# nrfMysensor.net
KiCad netlist of a schematic drawn in EAGLE
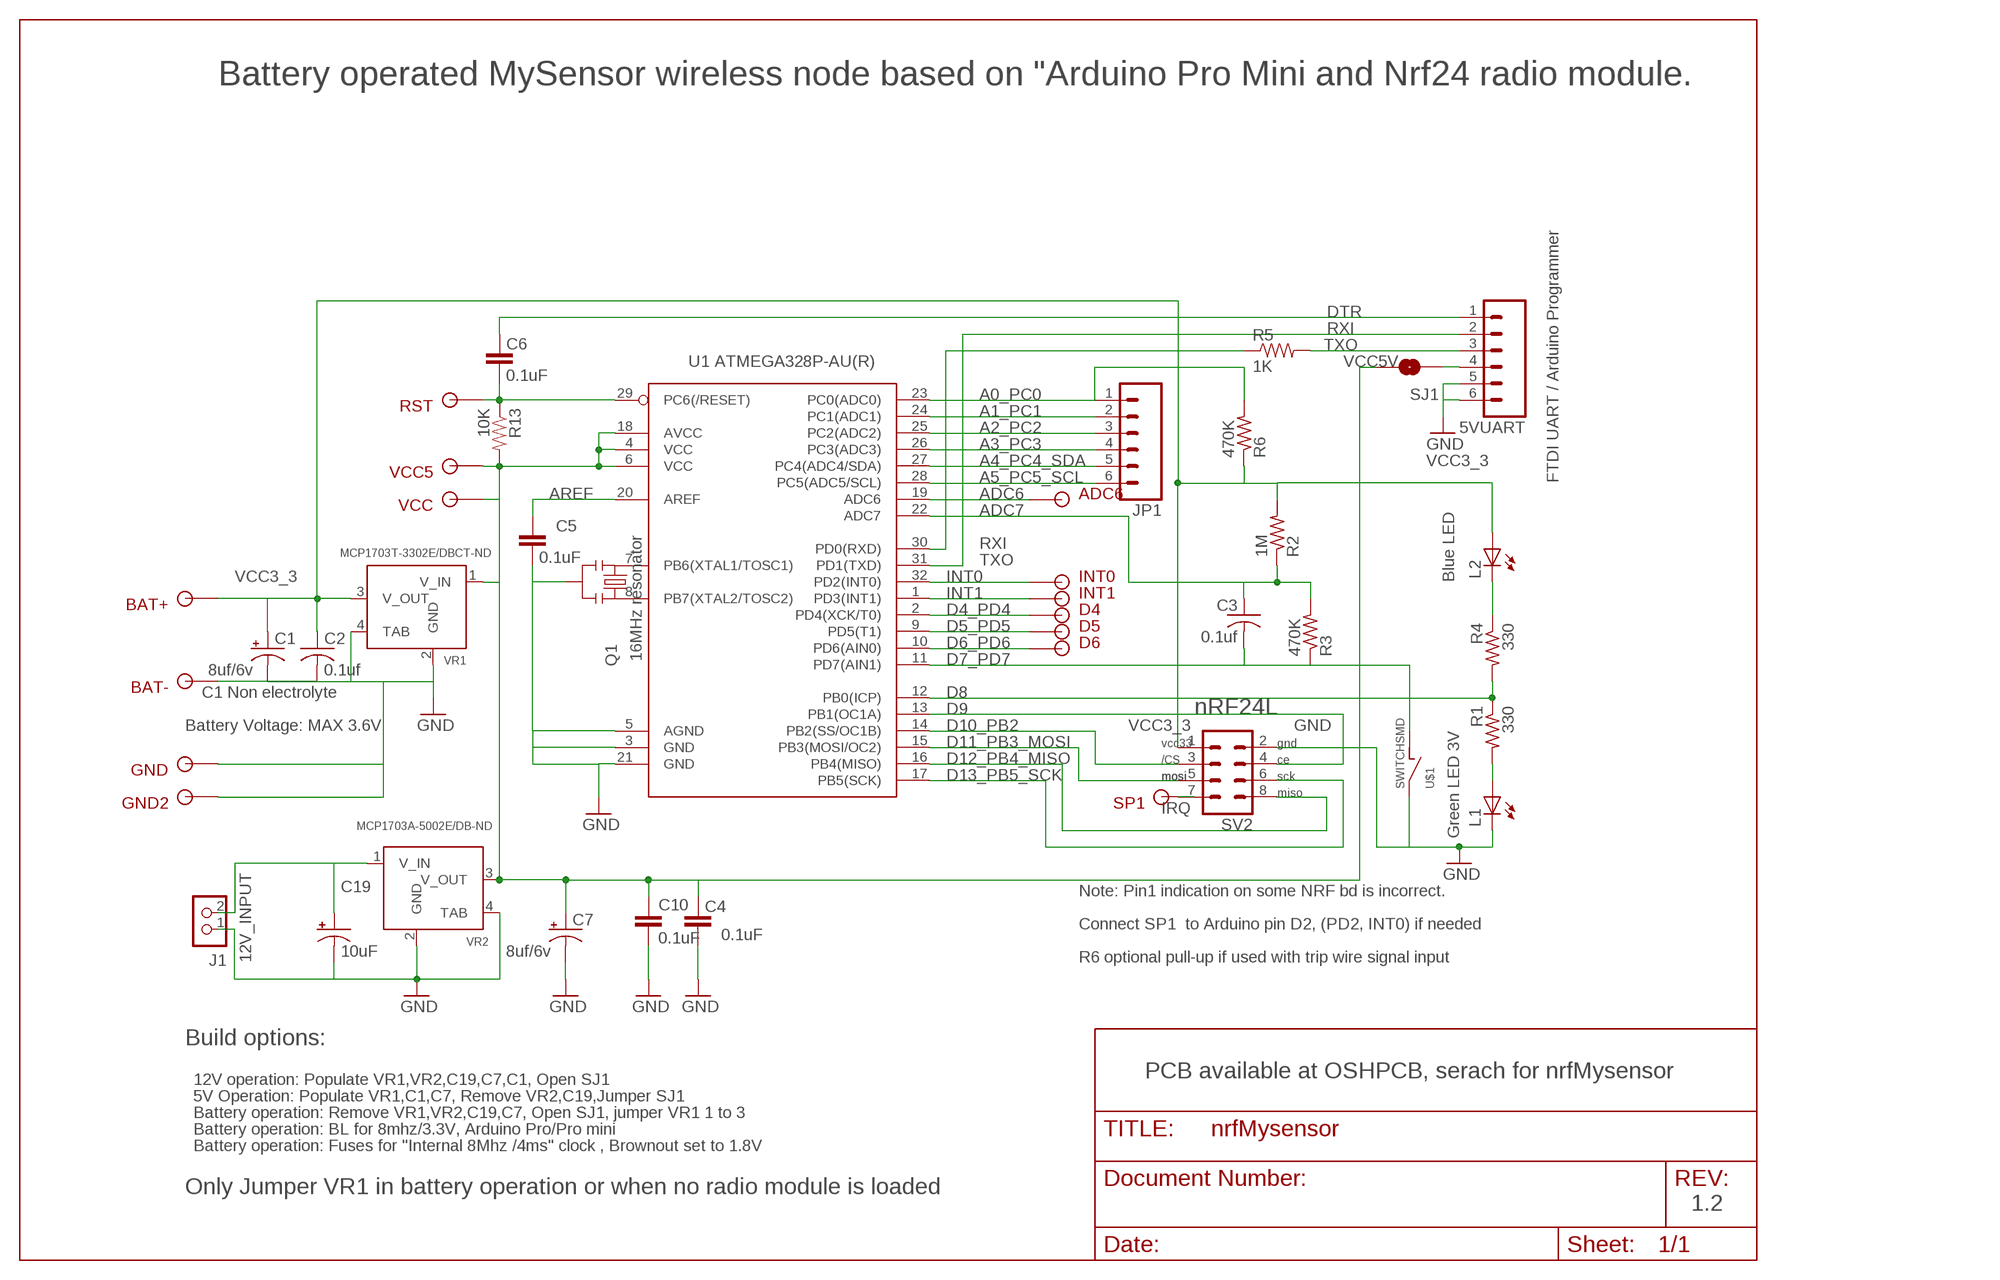
[diagram p0: schematic, sheet 1]

(export (version "E")
  (design (tool "Eeschema 10.0.6"))
  (components
    (comp (ref "5VUART")
      (value "M06SIP")
      (footprint "eagle-import:1X06")
      (libsource (lib "eagle-import") (part "M06SIP"))
    )
    (comp (ref "ADC6")
      (value "SOLDER_POINTA")
      (footprint "eagle-import:P1-13")
      (libsource (lib "eagle-import") (part "SOLDER_POINTA"))
    )
    (comp (ref "BAT+")
      (value "SOLDER_POINTA")
      (footprint "eagle-import:P1-13")
      (libsource (lib "eagle-import") (part "SOLDER_POINTA"))
    )
    (comp (ref "BAT-")
      (value "SOLDER_POINTA")
      (footprint "eagle-import:P1-13")
      (libsource (lib "eagle-import") (part "SOLDER_POINTA"))
    )
    (comp (ref "C1")
      (value "8uf/6v")
      (footprint "eagle-import:SMC_B")
      (libsource (lib "eagle-import") (part "CPOL-USSMCB"))
    )
    (comp (ref "C2")
      (value "0.1uf")
      (footprint "eagle-import:C0805")
      (libsource (lib "eagle-import") (part "C-USC0805"))
    )
    (comp (ref "C3")
      (value "0.1uf")
      (footprint "eagle-import:C0805")
      (libsource (lib "eagle-import") (part "C-USC0805"))
    )
    (comp (ref "C4")
      (value "0.1uF")
      (footprint "eagle-import:0805")
      (libsource (lib "eagle-import") (part "CAP0805"))
    )
    (comp (ref "C5")
      (value "0.1uF")
      (footprint "eagle-import:0805")
      (libsource (lib "eagle-import") (part "CAP0805"))
    )
    (comp (ref "C6")
      (value "0.1uF")
      (footprint "eagle-import:0805")
      (libsource (lib "eagle-import") (part "CAP0805"))
    )
    (comp (ref "C7")
      (value "8uf/6v")
      (footprint "eagle-import:SMC_B")
      (libsource (lib "eagle-import") (part "CPOL-USSMCB"))
    )
    (comp (ref "C10")
      (value "0.1uF")
      (footprint "eagle-import:0805")
      (libsource (lib "eagle-import") (part "CAP0805"))
    )
    (comp (ref "C19")
      (value "10uF")
      (footprint "eagle-import:EIA7343")
      (libsource (lib "eagle-import") (part "CAP_POL7343"))
    )
    (comp (ref "D4")
      (value "SOLDER_POINTA")
      (footprint "eagle-import:P1-13")
      (libsource (lib "eagle-import") (part "SOLDER_POINTA"))
    )
    (comp (ref "D5")
      (value "SOLDER_POINTA")
      (footprint "eagle-import:P1-13")
      (libsource (lib "eagle-import") (part "SOLDER_POINTA"))
    )
    (comp (ref "D6")
      (value "SOLDER_POINTA")
      (footprint "eagle-import:P1-13")
      (libsource (lib "eagle-import") (part "SOLDER_POINTA"))
    )
    (comp (ref "GND")
      (value "SOLDER_POINTA")
      (footprint "eagle-import:P1-13")
      (libsource (lib "eagle-import") (part "SOLDER_POINTA"))
    )
    (comp (ref "GND2")
      (value "SOLDER_POINTA")
      (footprint "eagle-import:P1-13")
      (libsource (lib "eagle-import") (part "SOLDER_POINTA"))
    )
    (comp (ref "INT0")
      (value "SOLDER_POINTA")
      (footprint "eagle-import:P1-13")
      (libsource (lib "eagle-import") (part "SOLDER_POINTA"))
    )
    (comp (ref "INT1")
      (value "SOLDER_POINTA")
      (footprint "eagle-import:P1-13")
      (libsource (lib "eagle-import") (part "SOLDER_POINTA"))
    )
    (comp (ref "J1")
      (value "12V input")
      (footprint "eagle-import:M1X2")
      (libsource (lib "eagle-import") (part "CON_HEADER_1X02-PTH"))
    )
    (comp (ref "JP1")
      (value "M06SIP")
      (footprint "eagle-import:1X06")
      (libsource (lib "eagle-import") (part "M06SIP"))
    )
    (comp (ref "L1")
      (value "LEDSML0603")
      (footprint "eagle-import:SML0603")
      (libsource (lib "eagle-import") (part "LEDSML0603"))
    )
    (comp (ref "L2")
      (value "LEDSML0603")
      (footprint "eagle-import:SML0603")
      (libsource (lib "eagle-import") (part "LEDSML0603"))
    )
    (comp (ref "Q1")
      (value "16MHz resonator")
      (footprint "eagle-import:RESONATOR-SMD")
      (libsource (lib "eagle-import") (part "RESONATORSMD"))
    )
    (comp (ref "R1")
      (value "330")
      (footprint "eagle-import:R0603")
      (libsource (lib "eagle-import") (part "R-US_R0603"))
    )
    (comp (ref "R2")
      (value "1M")
      (footprint "eagle-import:R0603")
      (libsource (lib "eagle-import") (part "R-US_R0603"))
    )
    (comp (ref "R3")
      (value "470K")
      (footprint "eagle-import:R0603")
      (libsource (lib "eagle-import") (part "R-US_R0603"))
    )
    (comp (ref "R4")
      (value "330")
      (footprint "eagle-import:R0603")
      (libsource (lib "eagle-import") (part "R-US_R0603"))
    )
    (comp (ref "R5")
      (value "1K")
      (footprint "eagle-import:0603")
      (libsource (lib "eagle-import") (part "RESISTOR0603"))
    )
    (comp (ref "R6")
      (value "470K")
      (footprint "eagle-import:R0603")
      (libsource (lib "eagle-import") (part "R-US_R0603"))
    )
    (comp (ref "R13")
      (value "10K")
      (footprint "eagle-import:0603")
      (libsource (lib "eagle-import") (part "RESISTOR0603"))
    )
    (comp (ref "RST")
      (value "SOLDER_POINTA")
      (footprint "eagle-import:P1-13")
      (libsource (lib "eagle-import") (part "SOLDER_POINTA"))
    )
    (comp (ref "SJ1")
      (value "SOLDERJUMPERNO")
      (footprint "eagle-import:SJ_2S-NO")
      (libsource (lib "eagle-import") (part "SOLDERJUMPERNO"))
    )
    (comp (ref "SP1")
      (value "SOLDER_POINTA")
      (footprint "eagle-import:P1-13")
      (libsource (lib "eagle-import") (part "SOLDER_POINTA"))
    )
    (comp (ref "SV2")
      (value "MA04-2")
      (footprint "eagle-import:MA04-2")
      (libsource (lib "eagle-import") (part "MA04-2"))
    )
    (comp (ref "U$1")
      (value "SWITCHSMD")
      (footprint "eagle-import:SMD_SWITCH")
      (libsource (lib "eagle-import") (part "SWITCHSMD"))
    )
    (comp (ref "U1")
      (value "ATMEGA328P-AU(R)")
      (footprint "eagle-import:TQFP32-08")
      (libsource (lib "eagle-import") (part "ATMEGA168"))
    )
    (comp (ref "VCC")
      (value "SOLDER_POINTA")
      (footprint "eagle-import:P1-13")
      (libsource (lib "eagle-import") (part "SOLDER_POINTA"))
    )
    (comp (ref "VCC5")
      (value "SOLDER_POINTA")
      (footprint "eagle-import:P1-13")
      (libsource (lib "eagle-import") (part "SOLDER_POINTA"))
    )
    (comp (ref "VR1")
      (value "MCP1703T-3302E/DBCT-ND")
      (footprint "eagle-import:SOT223")
      (libsource (lib "eagle-import") (part "MCP1703ASOT223"))
    )
    (comp (ref "VR2")
      (value "MCP1703A-5002E/DB-ND")
      (footprint "eagle-import:SOT223")
      (libsource (lib "eagle-import") (part "MCP1703ASOT223"))
    )
  )
  (nets
    (net (code "1") (name "/12V_INPUT") (class "Default")
      (node (ref "C19") (pin "A") (pinfunction "+_A") (pintype "passive"))
      (node (ref "J1") (pin "2") (pinfunction "2_2") (pintype "passive"))
      (node (ref "VR2") (pin "1") (pinfunction "V_IN_1") (pintype "bidirectional"))
    )
    (net (code "2") (name "/A0_PC0") (class "Default")
      (node (ref "JP1") (pin "1") (pinfunction "1_1") (pintype "passive"))
      (node (ref "R6") (pin "2") (pinfunction "2_2") (pintype "passive"))
      (node (ref "U1") (pin "23") (pinfunction "PC0(ADC0)_23") (pintype "bidirectional"))
    )
    (net (code "3") (name "/A1_PC1") (class "Default")
      (node (ref "JP1") (pin "2") (pinfunction "2_2") (pintype "passive"))
      (node (ref "U1") (pin "24") (pinfunction "PC1(ADC1)_24") (pintype "bidirectional"))
    )
    (net (code "4") (name "/A2_PC2") (class "Default")
      (node (ref "JP1") (pin "3") (pinfunction "3_3") (pintype "passive"))
      (node (ref "U1") (pin "25") (pinfunction "PC2(ADC2)_25") (pintype "bidirectional"))
    )
    (net (code "5") (name "/A3_PC3") (class "Default")
      (node (ref "JP1") (pin "4") (pinfunction "4_4") (pintype "passive"))
      (node (ref "U1") (pin "26") (pinfunction "PC3(ADC3)_26") (pintype "bidirectional"))
    )
    (net (code "6") (name "/A4_PC4_SDA") (class "Default")
      (node (ref "JP1") (pin "5") (pinfunction "5_5") (pintype "passive"))
      (node (ref "U1") (pin "27") (pinfunction "PC4(ADC4/SDA)_27") (pintype "bidirectional"))
    )
    (net (code "7") (name "/A5_PC5_SCL") (class "Default")
      (node (ref "JP1") (pin "6") (pinfunction "6_6") (pintype "passive"))
      (node (ref "U1") (pin "28") (pinfunction "PC5(ADC5/SCL)_28") (pintype "bidirectional"))
    )
    (net (code "8") (name "/ADC6") (class "Default")
      (node (ref "ADC6") (pin "1") (pinfunction "P$1_1") (pintype "bidirectional"))
      (node (ref "U1") (pin "19") (pinfunction "ADC6_19") (pintype "bidirectional"))
    )
    (net (code "9") (name "/ADC7") (class "Default")
      (node (ref "C3") (pin "1") (pinfunction "1_1") (pintype "passive"))
      (node (ref "R2") (pin "1") (pinfunction "1_1") (pintype "passive"))
      (node (ref "R3") (pin "2") (pinfunction "2_2") (pintype "passive"))
      (node (ref "U1") (pin "22") (pinfunction "ADC7_22") (pintype "bidirectional"))
    )
    (net (code "10") (name "/AREF") (class "Default")
      (node (ref "C5") (pin "2") (pinfunction "2_2") (pintype "passive"))
      (node (ref "U1") (pin "20") (pinfunction "AREF_20") (pintype "bidirectional"))
    )
    (net (code "11") (name "/D4_PD4") (class "Default")
      (node (ref "D4") (pin "1") (pinfunction "P$1_1") (pintype "bidirectional"))
      (node (ref "U1") (pin "2") (pinfunction "PD4(XCK/T0)_2") (pintype "bidirectional"))
    )
    (net (code "12") (name "/D5_PD5") (class "Default")
      (node (ref "D5") (pin "1") (pinfunction "P$1_1") (pintype "bidirectional"))
      (node (ref "U1") (pin "9") (pinfunction "PD5(T1)_9") (pintype "bidirectional"))
    )
    (net (code "13") (name "/D6_PD6") (class "Default")
      (node (ref "D6") (pin "1") (pinfunction "P$1_1") (pintype "bidirectional"))
      (node (ref "U1") (pin "10") (pinfunction "PD6(AIN0)_10") (pintype "bidirectional"))
    )
    (net (code "14") (name "/D7_PD7") (class "Default")
      (node (ref "C3") (pin "2") (pinfunction "2_2") (pintype "passive"))
      (node (ref "R3") (pin "1") (pinfunction "1_1") (pintype "passive"))
      (node (ref "U$1") (pin "P$1") (pinfunction "P$1_P$1") (pintype "passive"))
      (node (ref "U1") (pin "11") (pinfunction "PD7(AIN1)_11") (pintype "bidirectional"))
    )
    (net (code "15") (name "/D8") (class "Default")
      (node (ref "R1") (pin "1") (pinfunction "1_1") (pintype "passive"))
      (node (ref "R4") (pin "2") (pinfunction "2_2") (pintype "passive"))
      (node (ref "U1") (pin "12") (pinfunction "PB0(ICP)_12") (pintype "bidirectional"))
    )
    (net (code "16") (name "/D9") (class "Default")
      (node (ref "SV2") (pin "4") (pinfunction "4_4") (pintype "passive"))
      (node (ref "U1") (pin "13") (pinfunction "PB1(OC1A)_13") (pintype "bidirectional"))
    )
    (net (code "17") (name "/D10_PB2") (class "Default")
      (node (ref "SV2") (pin "3") (pinfunction "3_3") (pintype "passive"))
      (node (ref "U1") (pin "14") (pinfunction "PB2(SS/OC1B)_14") (pintype "bidirectional"))
    )
    (net (code "18") (name "/D11_PB3_MOSI") (class "Default")
      (node (ref "SV2") (pin "5") (pinfunction "5_5") (pintype "passive"))
      (node (ref "U1") (pin "15") (pinfunction "PB3(MOSI/OC2)_15") (pintype "bidirectional"))
    )
    (net (code "19") (name "/D12_PB4_MISO") (class "Default")
      (node (ref "SV2") (pin "8") (pinfunction "8_8") (pintype "passive"))
      (node (ref "U1") (pin "16") (pinfunction "PB4(MISO)_16") (pintype "bidirectional"))
    )
    (net (code "20") (name "/D13_PB5_SCK") (class "Default")
      (node (ref "SV2") (pin "6") (pinfunction "6_6") (pintype "passive"))
      (node (ref "U1") (pin "17") (pinfunction "PB5(SCK)_17") (pintype "bidirectional"))
    )
    (net (code "21") (name "/INT0") (class "Default")
      (node (ref "INT0") (pin "1") (pinfunction "P$1_1") (pintype "bidirectional"))
      (node (ref "U1") (pin "32") (pinfunction "PD2(INT0)_32") (pintype "bidirectional"))
    )
    (net (code "22") (name "/INT1") (class "Default")
      (node (ref "INT1") (pin "1") (pinfunction "P$1_1") (pintype "bidirectional"))
      (node (ref "U1") (pin "1") (pinfunction "PD3(INT1)_1") (pintype "bidirectional"))
    )
    (net (code "23") (name "/IRQ") (class "Default")
      (node (ref "SP1") (pin "1") (pinfunction "P$1_1") (pintype "bidirectional"))
      (node (ref "SV2") (pin "7") (pinfunction "7_7") (pintype "passive"))
    )
    (net (code "24") (name "/RXI") (class "Default")
      (node (ref "R5") (pin "1") (pinfunction "1_1") (pintype "passive"))
      (node (ref "U1") (pin "30") (pinfunction "PD0(RXD)_30") (pintype "bidirectional"))
    )
    (net (code "25") (name "/TXO") (class "Default")
      (node (ref "5VUART") (pin "2") (pinfunction "2_2") (pintype "passive"))
      (node (ref "U1") (pin "31") (pinfunction "PD1(TXD)_31") (pintype "bidirectional"))
    )
    (net (code "26") (name "/VCC3_3") (class "Default")
      (node (ref "BAT+") (pin "1") (pinfunction "P$1_1") (pintype "bidirectional"))
      (node (ref "C1") (pin "+") (pinfunction "+_+") (pintype "passive"))
      (node (ref "C2") (pin "1") (pinfunction "1_1") (pintype "passive"))
      (node (ref "L2") (pin "A") (pinfunction "A_A") (pintype "passive"))
      (node (ref "R2") (pin "2") (pinfunction "2_2") (pintype "passive"))
      (node (ref "R6") (pin "1") (pinfunction "1_1") (pintype "passive"))
      (node (ref "SV2") (pin "1") (pinfunction "1_1") (pintype "passive"))
      (node (ref "VR1") (pin "3") (pinfunction "V_OUT_3") (pintype "bidirectional"))
    )
    (net (code "27") (name "GND") (class "Default")
      (node (ref "5VUART") (pin "5") (pinfunction "5_5") (pintype "passive"))
      (node (ref "5VUART") (pin "6") (pinfunction "6_6") (pintype "passive"))
      (node (ref "BAT-") (pin "1") (pinfunction "P$1_1") (pintype "bidirectional"))
      (node (ref "C1") (pin "-") (pinfunction "-_-") (pintype "passive"))
      (node (ref "C10") (pin "2") (pinfunction "2_2") (pintype "passive"))
      (node (ref "C19") (pin "C") (pinfunction "-_C") (pintype "passive"))
      (node (ref "C2") (pin "2") (pinfunction "2_2") (pintype "passive"))
      (node (ref "C4") (pin "1") (pinfunction "1_1") (pintype "passive"))
      (node (ref "C5") (pin "1") (pinfunction "1_1") (pintype "passive"))
      (node (ref "C7") (pin "-") (pinfunction "-_-") (pintype "passive"))
      (node (ref "GND") (pin "1") (pinfunction "P$1_1") (pintype "bidirectional"))
      (node (ref "GND2") (pin "1") (pinfunction "P$1_1") (pintype "bidirectional"))
      (node (ref "J1") (pin "1") (pinfunction "1_1") (pintype "passive"))
      (node (ref "L1") (pin "C") (pinfunction "C_C") (pintype "passive"))
      (node (ref "Q1") (pin "2") (pinfunction "2_2") (pintype "passive"))
      (node (ref "SV2") (pin "2") (pinfunction "2_2") (pintype "passive"))
      (node (ref "U$1") (pin "P$2") (pinfunction "P$2_P$2") (pintype "passive"))
      (node (ref "U1") (pin "21") (pinfunction "GND_21") (pintype "bidirectional"))
      (node (ref "U1") (pin "3") (pinfunction "GND_3") (pintype "bidirectional"))
      (node (ref "U1") (pin "5") (pinfunction "AGND_5") (pintype "bidirectional"))
      (node (ref "VR1") (pin "2") (pinfunction "GND_2") (pintype "bidirectional"))
      (node (ref "VR1") (pin "4") (pinfunction "TAB_4") (pintype "bidirectional"))
      (node (ref "VR2") (pin "2") (pinfunction "GND_2") (pintype "bidirectional"))
      (node (ref "VR2") (pin "4") (pinfunction "TAB_4") (pintype "bidirectional"))
    )
    (net (code "28") (name "Net-(5VUART-Pad1)") (class "Default")
      (node (ref "5VUART") (pin "1") (pinfunction "1_1") (pintype "passive"))
      (node (ref "C6") (pin "2") (pinfunction "2_2") (pintype "passive"))
    )
    (net (code "29") (name "Net-(5VUART-Pad3)") (class "Default")
      (node (ref "5VUART") (pin "3") (pinfunction "3_3") (pintype "passive"))
      (node (ref "R5") (pin "2") (pinfunction "2_2") (pintype "passive"))
    )
    (net (code "30") (name "Net-(5VUART-Pad4)") (class "Default")
      (node (ref "5VUART") (pin "4") (pinfunction "4_4") (pintype "passive"))
      (node (ref "SJ1") (pin "2") (pinfunction "2_2") (pintype "passive"))
    )
    (net (code "31") (name "Net-(L1-PadA)") (class "Default")
      (node (ref "L1") (pin "A") (pinfunction "A_A") (pintype "passive"))
      (node (ref "R1") (pin "2") (pinfunction "2_2") (pintype "passive"))
    )
    (net (code "32") (name "Net-(L2-PadC)") (class "Default")
      (node (ref "L2") (pin "C") (pinfunction "C_C") (pintype "passive"))
      (node (ref "R4") (pin "1") (pinfunction "1_1") (pintype "passive"))
    )
    (net (code "33") (name "Net-(RST-P$1)") (class "Default")
      (node (ref "C6") (pin "1") (pinfunction "1_1") (pintype "passive"))
      (node (ref "R13") (pin "1") (pinfunction "1_1") (pintype "passive"))
      (node (ref "RST") (pin "1") (pinfunction "P$1_1") (pintype "bidirectional"))
      (node (ref "U1") (pin "29") (pinfunction "PC6(/RESET)_29") (pintype "bidirectional"))
    )
    (net (code "34") (name "Net-(U1-AVCC)") (class "Default")
      (node (ref "C10") (pin "1") (pinfunction "1_1") (pintype "passive"))
      (node (ref "C4") (pin "2") (pinfunction "2_2") (pintype "passive"))
      (node (ref "C7") (pin "+") (pinfunction "+_+") (pintype "passive"))
      (node (ref "R13") (pin "2") (pinfunction "2_2") (pintype "passive"))
      (node (ref "SJ1") (pin "1") (pinfunction "1_1") (pintype "passive"))
      (node (ref "U1") (pin "18") (pinfunction "AVCC_18") (pintype "bidirectional"))
      (node (ref "U1") (pin "4") (pinfunction "VCC_4") (pintype "bidirectional"))
      (node (ref "U1") (pin "6") (pinfunction "VCC_6") (pintype "bidirectional"))
      (node (ref "VCC") (pin "1") (pinfunction "P$1_1") (pintype "bidirectional"))
      (node (ref "VCC5") (pin "1") (pinfunction "P$1_1") (pintype "bidirectional"))
      (node (ref "VR1") (pin "1") (pinfunction "V_IN_1") (pintype "bidirectional"))
      (node (ref "VR2") (pin "3") (pinfunction "V_OUT_3") (pintype "bidirectional"))
    )
    (net (code "35") (name "Net-(U1-PB6(XTAL1{slash}TOSC1))") (class "Default")
      (node (ref "Q1") (pin "3") (pinfunction "3_3") (pintype "passive"))
      (node (ref "U1") (pin "7") (pinfunction "PB6(XTAL1/TOSC1)_7") (pintype "bidirectional"))
    )
    (net (code "36") (name "Net-(U1-PB7(XTAL2{slash}TOSC2))") (class "Default")
      (node (ref "Q1") (pin "1") (pinfunction "1_1") (pintype "passive"))
      (node (ref "U1") (pin "8") (pinfunction "PB7(XTAL2/TOSC2)_8") (pintype "bidirectional"))
    )
  )
)
